# Self_Balancing_esp32cam.net
KiCad netlist of a schematic drawn in EAGLE
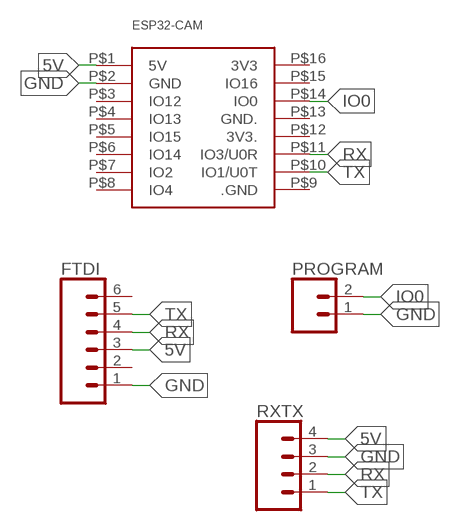
[diagram p0: schematic, sheet 1]

(export (version "E")
  (design (tool "Eeschema 10.0.6"))
  (components
    (comp (ref "ESP32-CAM")
      (value "ESP32-CAM")
      (footprint "eagle-import:ESP32-CAM")
      (fields (field (name "MF") "AI-Thinker"))
      (libsource (lib "eagle-import") (part "ESP32-CAM"))
    )
    (comp (ref "FTDI")
      (value "CONN_06SILK_FEMALE_PTH")
      (footprint "eagle-import:1X06")
      (libsource (lib "eagle-import") (part "CONN_06SILK_FEMALE_PTH"))
    )
    (comp (ref "PROGRAM")
      (value "CONN_02")
      (footprint "eagle-import:1X02")
      (libsource (lib "eagle-import") (part "CONN_02"))
    )
    (comp (ref "RXTX")
      (value "CONN_04PTH")
      (footprint "eagle-import:1X04")
      (libsource (lib "eagle-import") (part "CONN_04PTH"))
    )
  )
  (nets
    (net (code "1") (name "5V") (class "Default")
      (node (ref "ESP32-CAM") (pin "P$1") (pinfunction "5V_P$1") (pintype "bidirectional"))
      (node (ref "FTDI") (pin "3") (pinfunction "3_3") (pintype "passive"))
      (node (ref "RXTX") (pin "4") (pinfunction "4_4") (pintype "passive"))
    )
    (net (code "2") (name "GND") (class "Default")
      (node (ref "ESP32-CAM") (pin "P$2") (pinfunction "GND_P$2") (pintype "bidirectional"))
      (node (ref "FTDI") (pin "1") (pinfunction "1_1") (pintype "passive"))
      (node (ref "PROGRAM") (pin "1") (pinfunction "1_1") (pintype "passive"))
      (node (ref "RXTX") (pin "3") (pinfunction "3_3") (pintype "passive"))
    )
    (net (code "3") (name "IO0") (class "Default")
      (node (ref "ESP32-CAM") (pin "P$14") (pinfunction "IO0_P$14") (pintype "bidirectional"))
      (node (ref "PROGRAM") (pin "2") (pinfunction "2_2") (pintype "passive"))
    )
    (net (code "4") (name "RX") (class "Default")
      (node (ref "ESP32-CAM") (pin "P$11") (pinfunction "IO3/U0R_P$11") (pintype "bidirectional"))
      (node (ref "FTDI") (pin "4") (pinfunction "4_4") (pintype "passive"))
      (node (ref "RXTX") (pin "2") (pinfunction "2_2") (pintype "passive"))
    )
    (net (code "5") (name "TX") (class "Default")
      (node (ref "ESP32-CAM") (pin "P$10") (pinfunction "IO1/U0T_P$10") (pintype "bidirectional"))
      (node (ref "FTDI") (pin "5") (pinfunction "5_5") (pintype "passive"))
      (node (ref "RXTX") (pin "1") (pinfunction "1_1") (pintype "passive"))
    )
    (net (code "6") (name "unconnected-(ESP32-CAM-.GND-PadP$9)") (class "Default")
      (node (ref "ESP32-CAM") (pin "P$9") (pinfunction ".GND_P$9") (pintype "bidirectional"))
    )
    (net (code "7") (name "unconnected-(ESP32-CAM-3V3-PadP$16)") (class "Default")
      (node (ref "ESP32-CAM") (pin "P$16") (pinfunction "3V3_P$16") (pintype "bidirectional"))
    )
    (net (code "8") (name "unconnected-(ESP32-CAM-3V3.-PadP$12)") (class "Default")
      (node (ref "ESP32-CAM") (pin "P$12") (pinfunction "3V3._P$12") (pintype "bidirectional"))
    )
    (net (code "9") (name "unconnected-(ESP32-CAM-GND.-PadP$13)") (class "Default")
      (node (ref "ESP32-CAM") (pin "P$13") (pinfunction "GND._P$13") (pintype "bidirectional"))
    )
    (net (code "10") (name "unconnected-(ESP32-CAM-IO2-PadP$7)") (class "Default")
      (node (ref "ESP32-CAM") (pin "P$7") (pinfunction "IO2_P$7") (pintype "bidirectional"))
    )
    (net (code "11") (name "unconnected-(ESP32-CAM-IO4-PadP$8)") (class "Default")
      (node (ref "ESP32-CAM") (pin "P$8") (pinfunction "IO4_P$8") (pintype "bidirectional"))
    )
    (net (code "12") (name "unconnected-(ESP32-CAM-IO12-PadP$3)") (class "Default")
      (node (ref "ESP32-CAM") (pin "P$3") (pinfunction "IO12_P$3") (pintype "bidirectional"))
    )
    (net (code "13") (name "unconnected-(ESP32-CAM-IO13-PadP$4)") (class "Default")
      (node (ref "ESP32-CAM") (pin "P$4") (pinfunction "IO13_P$4") (pintype "bidirectional"))
    )
    (net (code "14") (name "unconnected-(ESP32-CAM-IO14-PadP$6)") (class "Default")
      (node (ref "ESP32-CAM") (pin "P$6") (pinfunction "IO14_P$6") (pintype "bidirectional"))
    )
    (net (code "15") (name "unconnected-(ESP32-CAM-IO15-PadP$5)") (class "Default")
      (node (ref "ESP32-CAM") (pin "P$5") (pinfunction "IO15_P$5") (pintype "bidirectional"))
    )
    (net (code "16") (name "unconnected-(ESP32-CAM-IO16-PadP$15)") (class "Default")
      (node (ref "ESP32-CAM") (pin "P$15") (pinfunction "IO16_P$15") (pintype "bidirectional"))
    )
    (net (code "17") (name "unconnected-(FTDI-Pad2)") (class "Default")
      (node (ref "FTDI") (pin "2") (pinfunction "2_2") (pintype "passive"))
    )
    (net (code "18") (name "unconnected-(FTDI-Pad6)") (class "Default")
      (node (ref "FTDI") (pin "6") (pinfunction "6_6") (pintype "passive"))
    )
  )
)
